# M_ch_Thu.net
KiCad netlist of a schematic drawn in Altium Designer
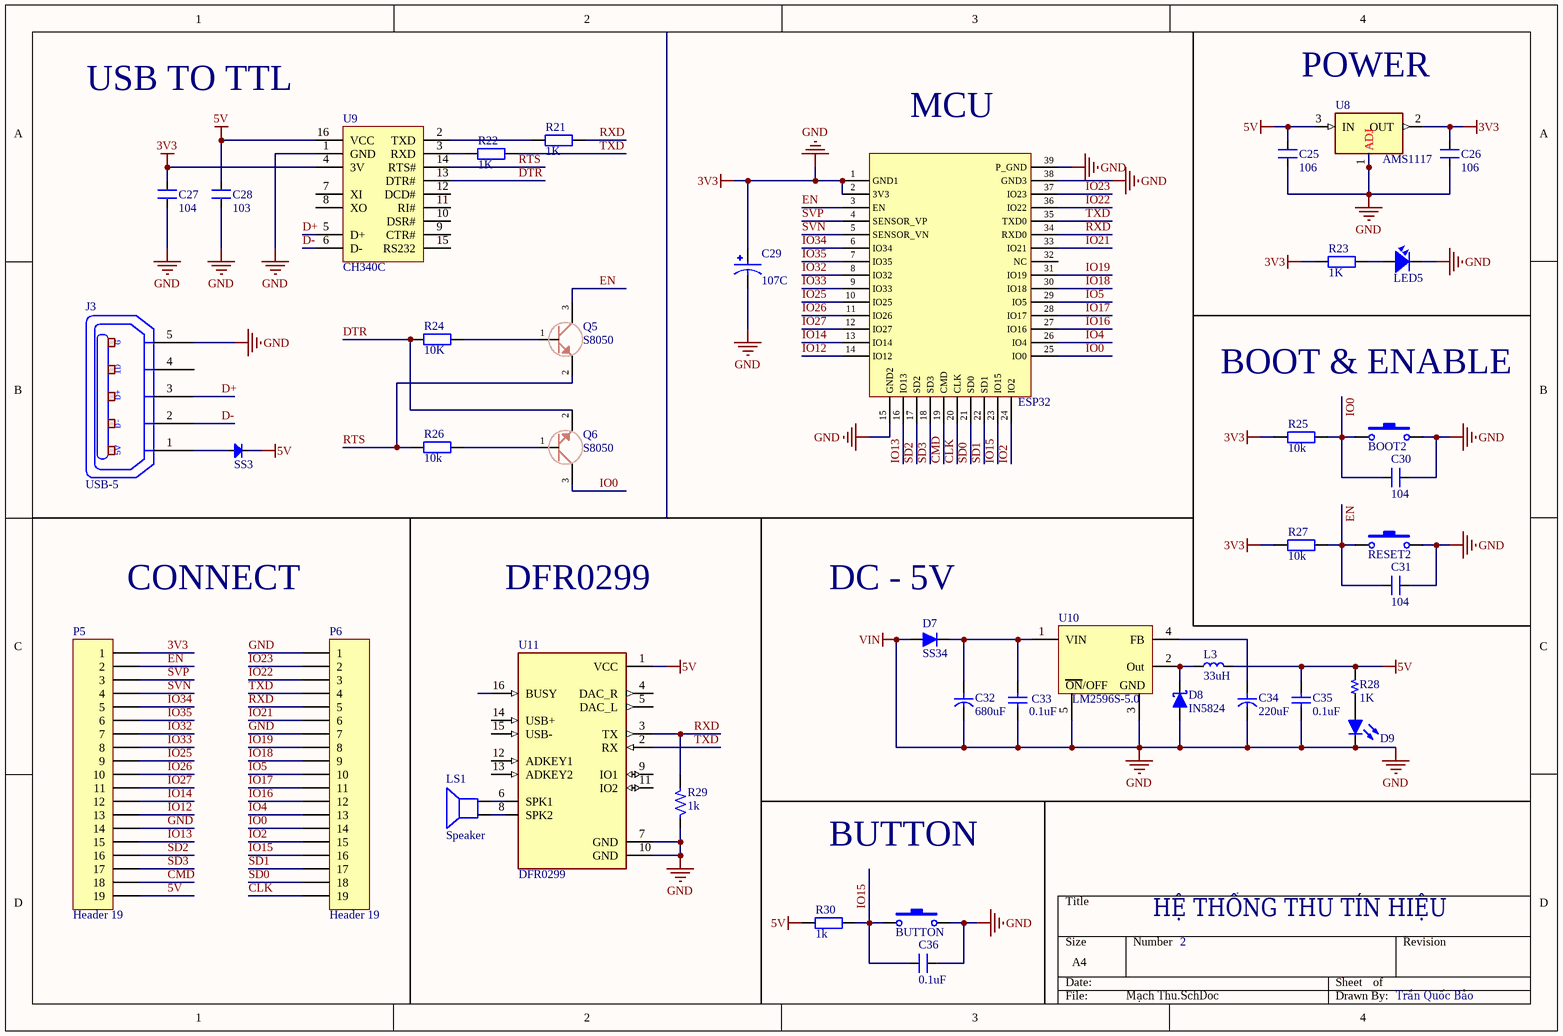
[diagram p0: Mạch Thu.SchDoc]

(export (version "E")
  (design (tool "Eeschema 10.0.6"))
  (components
    (comp (ref "BOOT2")
      (value "SW-SMD")
      (footprint "SW-SMD")
      (description "Switch")
      (fields (field (name "PUBLISHER") "Altium Limited"))
      (libsource (lib "My Library") (part "SW-SMD"))
    )
    (comp (ref "BUTTON")
      (value "SW-SMD")
      (footprint "SW-SMD")
      (description "Switch")
      (fields (field (name "PUBLISHER") "Altium Limited"))
      (libsource (lib "My Library") (part "SW-SMD"))
    )
    (comp (ref "C25")
      (value "106")
      (footprint "SM-0805")
      (description "Cap SMD")
      (libsource (lib "My Library") (part "CM"))
    )
    (comp (ref "C26")
      (value "106")
      (footprint "SM-0805")
      (description "Cap SMD")
      (libsource (lib "My Library") (part "CM"))
    )
    (comp (ref "C27")
      (value "104")
      (footprint "SM-0805")
      (description "Cap SMD")
      (libsource (lib "My Library") (part "CM"))
    )
    (comp (ref "C28")
      (value "103")
      (footprint "SM-0805")
      (description "Cap SMD")
      (libsource (lib "My Library") (part "CM"))
    )
    (comp (ref "C29")
      (value "107C")
      (footprint "CAP_TANTALUM_3528")
      (description "Capacitor, Tantalum")
      (fields (field (name "MF") "AVX") (field (name "MP") "TAJB475K025RNJ"))
      (libsource (lib "My Library") (part "CAP_TANTALUM_SMD"))
    )
    (comp (ref "C30")
      (value "104")
      (footprint "SM-0805")
      (description "Cap SMD")
      (libsource (lib "My Library") (part "CM"))
    )
    (comp (ref "C31")
      (value "104")
      (footprint "SM-0805")
      (description "Cap SMD")
      (libsource (lib "My Library") (part "CM"))
    )
    (comp (ref "C32")
      (value "680uF")
      (footprint "C SMD TAN 1206 (A)")
      (description "Capacitor pol")
      (libsource (lib "chipfc_altium_libs") (part "Capacitor"))
    )
    (comp (ref "C33")
      (value "0.1uF")
      (footprint "C 0805")
      (description "Capacitor non-pol")
      (libsource (lib "chipfc_altium_libs") (part "Capacitor NP"))
    )
    (comp (ref "C34")
      (value "220uF")
      (footprint "C SMD TAN 1206 (A)")
      (description "Capacitor pol")
      (libsource (lib "chipfc_altium_libs") (part "Capacitor"))
    )
    (comp (ref "C35")
      (value "0.1uF")
      (footprint "C 0805")
      (description "Capacitor non-pol")
      (libsource (lib "chipfc_altium_libs") (part "Capacitor NP"))
    )
    (comp (ref "C36")
      (value "0.1uF")
      (footprint "SM-0805")
      (description "Cap SMD")
      (libsource (lib "My Library") (part "CM"))
    )
    (comp (ref "D7")
      (value "SS34")
      (footprint "DO-35 (SOD27 )")
      (description "Default Diode")
      (libsource (lib "chipfc_altium_libs") (part "Diode"))
    )
    (comp (ref "D8")
      (value "IN5824")
      (footprint "DO-41")
      (description "Schottky Diode")
      (libsource (lib "chipfc_altium_libs") (part "Diode Schottky"))
    )
    (comp (ref "D9")
      (value "Led")
      (footprint "Led 0805 RED")
      (description "Typical LED")
      (libsource (lib "chipfc_altium_libs") (part "Led"))
    )
    (comp (ref "ESP32")
      (value "ESP32")
      (footprint "My Library:ESP_WROOM_32")
      (libsource (lib "My Library") (part "ESP-WROOM-32"))
    )
    (comp (ref "J3")
      (value "USB-5")
      (footprint "USB-M1")
      (fields
        (field (name "MANUFACTURER") "FCI")
        (field (name "MANUFACTURER PART NUMBER") "10118193-0001LF")
        (field (name ".CREATOR") "MM")
        (field (name ".CHECKED PCB") "RF")
        (field (name ".CHECKED SCH") "MM")
      )
      (libsource (lib "My Library") (part "USB-5"))
    )
    (comp (ref "L3")
      (value "33uH")
      (footprint "Inductor SMD 12x12x8")
      (description "Inductor")
      (libsource (lib "chipfc_altium_libs") (part "Inductor"))
    )
    (comp (ref "LED5") (value "LED") (footprint "LED 3512") (libsource (lib "My Library") (part "LED SMD")))
    (comp (ref "LS1")
      (value "Speaker")
      (footprint "SPEAKER")
      (description "Loudspeaker")
      (fields (field (name "PUBLISHER") "Altium Limited"))
      (libsource (lib "My Library") (part "Speaker"))
    )
    (comp (ref "P5")
      (value "Header 19")
      (footprint "HDR1X19")
      (description "Header, 19-Pin")
      (fields (field (name "PUBLISHER") "Altium Limited"))
      (libsource (lib "") (part "Header 19_1"))
    )
    (comp (ref "P6")
      (value "Header 19")
      (footprint "HDR1X19")
      (description "Header, 19-Pin")
      (fields (field (name "PUBLISHER") "Altium Limited"))
      (libsource (lib "My Library") (part "Header 19"))
    )
    (comp (ref "Q5")
      (value "S8050")
      (footprint "SOT23")
      (libsource (lib "My Library") (part "Transitor SMD"))
    )
    (comp (ref "Q6")
      (value "S8050")
      (footprint "SOT23")
      (libsource (lib "My Library") (part "Transitor SMD"))
    )
    (comp (ref "R21")
      (value "1K")
      (footprint "DIEN TRO 0805")
      (description "Resistor SMD 0805")
      (fields (field (name "Comment") "R0805") (field (name "PUBLISHER") "Altium Limited"))
      (libsource (lib "My Library") (part "R0805"))
    )
    (comp (ref "R22")
      (value "1K")
      (footprint "DIEN TRO 0805")
      (description "Resistor SMD 0805")
      (fields (field (name "Comment") "R0805") (field (name "PUBLISHER") "Altium Limited"))
      (libsource (lib "My Library") (part "R0805"))
    )
    (comp (ref "R23")
      (value "1K")
      (footprint "DIEN TRO 0805")
      (description "Resistor SMD 0805")
      (fields (field (name "Comment") "R0805") (field (name "PUBLISHER") "Altium Limited"))
      (libsource (lib "My Library") (part "R0805"))
    )
    (comp (ref "R24")
      (value "10K")
      (footprint "DIEN TRO 0805")
      (description "Resistor SMD 0805")
      (fields (field (name "Comment") "R0805") (field (name "PUBLISHER") "Altium Limited"))
      (libsource (lib "My Library") (part "R0805"))
    )
    (comp (ref "R25")
      (value "10k")
      (footprint "DIEN TRO 0805")
      (description "Resistor SMD 0805")
      (fields (field (name "Comment") "R0805") (field (name "PUBLISHER") "Altium Limited"))
      (libsource (lib "My Library") (part "R0805"))
    )
    (comp (ref "R26")
      (value "10k")
      (footprint "DIEN TRO 0805")
      (description "Resistor SMD 0805")
      (fields (field (name "Comment") "R0805") (field (name "PUBLISHER") "Altium Limited"))
      (libsource (lib "My Library") (part "R0805"))
    )
    (comp (ref "R27")
      (value "10k")
      (footprint "DIEN TRO 0805")
      (description "Resistor SMD 0805")
      (fields (field (name "Comment") "R0805") (field (name "PUBLISHER") "Altium Limited"))
      (libsource (lib "My Library") (part "R0805"))
    )
    (comp (ref "R28")
      (value "1K")
      (footprint "R 0805")
      (description "Resistor")
      (libsource (lib "chipfc_altium_libs") (part "Resistor"))
    )
    (comp (ref "R29")
      (value "1k")
      (footprint "R1/8W")
      (description "Resistor 1/4W")
      (libsource (lib "My Library") (part "R"))
    )
    (comp (ref "R30")
      (value "1k")
      (footprint "DIEN TRO 0805")
      (description "Resistor SMD 0805")
      (fields (field (name "Comment") "R0805") (field (name "PUBLISHER") "Altium Limited"))
      (libsource (lib "My Library") (part "R0805"))
    )
    (comp (ref "RESET2")
      (value "SW-SMD")
      (footprint "SW-SMD")
      (description "Switch")
      (fields (field (name "PUBLISHER") "Altium Limited"))
      (libsource (lib "My Library") (part "SW-SMD"))
    )
    (comp (ref "SS3")
      (value "Diode SMD")
      (footprint "DIO-SMD-106")
      (description "Default Diode")
      (fields (field (name "PUBLISHER") "Altium Limited"))
      (libsource (lib "My Library") (part "Diode SMD"))
    )
    (comp (ref "U8")
      (value "AMS1117")
      (footprint "SOT223-4N")
      (description "IC")
      (libsource (lib "My Library") (part "AMS1117"))
    )
    (comp (ref "U9")
      (value "CH340C")
      (footprint "SO16")
      (description "High and Low Side Driver")
      (fields (field (name "PUBLISHER") "Altium Limited"))
      (libsource (lib "My Library") (part "CH340G"))
    )
    (comp (ref "U10")
      (value "LM2596S-5.0")
      (footprint "TO-263-5")
      (description "Simple Switcher 3A Step-Down Voltage Regulator")
      (libsource (lib "chipfc_altium_libs") (part "LM2596S-5.0"))
    )
    (comp (ref "U11")
      (value "DFR0299")
      (footprint "MODULE_DFR0299")
      (description "Dfplayer - a Mini Mp3 Player")
      (libsource (lib "DFR0299") (part "DFR0299"))
    )
  )
  (nets
    (net (code "1") (name "/CLK") (class "Default")
      (node (ref "ESP32") (pin "20") (pinfunction "CLK_20") (pintype "passive"))
      (node (ref "P6") (pin "19") (pinfunction "19_19") (pintype "passive"))
    )
    (net (code "2") (name "/CMD") (class "Default")
      (node (ref "ESP32") (pin "19") (pinfunction "CMD_19") (pintype "passive"))
      (node (ref "P5") (pin "18") (pinfunction "18_18") (pintype "passive"))
    )
    (net (code "3") (name "/D+") (class "Default")
      (node (ref "J3") (pin "3") (pinfunction "P3_3") (pintype "passive"))
      (node (ref "U9") (pin "5") (pinfunction "D+_5") (pintype "passive"))
    )
    (net (code "4") (name "/D-") (class "Default")
      (node (ref "J3") (pin "2") (pinfunction "P2_2") (pintype "passive"))
      (node (ref "U9") (pin "6") (pinfunction "D-_6") (pintype "passive"))
    )
    (net (code "5") (name "/DTR") (class "Default")
      (node (ref "Q6") (pin "2") (pinfunction "E_2") (pintype "passive"))
      (node (ref "R24") (pin "1") (pinfunction "1_1") (pintype "passive"))
      (node (ref "U9") (pin "13") (pinfunction "DTR#_13") (pintype "passive"))
    )
    (net (code "6") (name "/EN") (class "Default")
      (node (ref "C31") (pin "2") (pinfunction "2_2") (pintype "passive"))
      (node (ref "ESP32") (pin "3") (pinfunction "EN_3") (pintype "passive"))
      (node (ref "P5") (pin "2") (pinfunction "2_2") (pintype "passive"))
      (node (ref "Q5") (pin "3") (pinfunction "C_3") (pintype "passive"))
      (node (ref "R27") (pin "2") (pinfunction "2_2") (pintype "passive"))
      (node (ref "RESET2") (pin "1") (pinfunction "1_1") (pintype "passive"))
    )
    (net (code "7") (name "/IO0") (class "Default")
      (node (ref "BOOT2") (pin "1") (pinfunction "1_1") (pintype "passive"))
      (node (ref "C30") (pin "2") (pinfunction "2_2") (pintype "passive"))
      (node (ref "ESP32") (pin "25") (pinfunction "IO0_25") (pintype "passive"))
      (node (ref "P6") (pin "14") (pinfunction "14_14") (pintype "passive"))
      (node (ref "Q6") (pin "3") (pinfunction "C_3") (pintype "passive"))
      (node (ref "R25") (pin "2") (pinfunction "2_2") (pintype "passive"))
    )
    (net (code "8") (name "/IO2") (class "Default")
      (node (ref "ESP32") (pin "24") (pinfunction "IO2_24") (pintype "passive"))
      (node (ref "P6") (pin "15") (pinfunction "15_15") (pintype "passive"))
    )
    (net (code "9") (name "/IO4") (class "Default")
      (node (ref "ESP32") (pin "26") (pinfunction "IO4_26") (pintype "passive"))
      (node (ref "P6") (pin "13") (pinfunction "13_13") (pintype "passive"))
    )
    (net (code "10") (name "/IO5") (class "Default")
      (node (ref "ESP32") (pin "29") (pinfunction "IO5_29") (pintype "passive"))
      (node (ref "P6") (pin "10") (pinfunction "10_10") (pintype "passive"))
    )
    (net (code "11") (name "/IO12") (class "Default")
      (node (ref "ESP32") (pin "14") (pinfunction "IO12_14") (pintype "passive"))
      (node (ref "P5") (pin "13") (pinfunction "13_13") (pintype "passive"))
    )
    (net (code "12") (name "/IO13") (class "Default")
      (node (ref "ESP32") (pin "16") (pinfunction "IO13_16") (pintype "passive"))
      (node (ref "P5") (pin "15") (pinfunction "15_15") (pintype "passive"))
    )
    (net (code "13") (name "/IO14") (class "Default")
      (node (ref "ESP32") (pin "13") (pinfunction "IO14_13") (pintype "passive"))
      (node (ref "P5") (pin "12") (pinfunction "12_12") (pintype "passive"))
    )
    (net (code "14") (name "/IO15") (class "Default")
      (node (ref "BUTTON") (pin "1") (pinfunction "1_1") (pintype "passive"))
      (node (ref "C36") (pin "2") (pinfunction "2_2") (pintype "passive"))
      (node (ref "ESP32") (pin "23") (pinfunction "IO15_23") (pintype "passive"))
      (node (ref "P6") (pin "16") (pinfunction "16_16") (pintype "passive"))
      (node (ref "R30") (pin "2") (pinfunction "2_2") (pintype "passive"))
    )
    (net (code "15") (name "/IO16") (class "Default")
      (node (ref "ESP32") (pin "27") (pinfunction "IO16_27") (pintype "passive"))
      (node (ref "P6") (pin "12") (pinfunction "12_12") (pintype "passive"))
    )
    (net (code "16") (name "/IO17") (class "Default")
      (node (ref "ESP32") (pin "28") (pinfunction "IO17_28") (pintype "passive"))
      (node (ref "P6") (pin "11") (pinfunction "11_11") (pintype "passive"))
    )
    (net (code "17") (name "/IO18") (class "Default")
      (node (ref "ESP32") (pin "30") (pinfunction "IO18_30") (pintype "passive"))
      (node (ref "P6") (pin "9") (pinfunction "9_9") (pintype "passive"))
    )
    (net (code "18") (name "/IO19") (class "Default")
      (node (ref "ESP32") (pin "31") (pinfunction "IO19_31") (pintype "passive"))
      (node (ref "P6") (pin "8") (pinfunction "8_8") (pintype "passive"))
    )
    (net (code "19") (name "/IO21") (class "Default")
      (node (ref "ESP32") (pin "33") (pinfunction "IO21_33") (pintype "passive"))
      (node (ref "P6") (pin "6") (pinfunction "6_6") (pintype "passive"))
    )
    (net (code "20") (name "/IO22") (class "Default")
      (node (ref "ESP32") (pin "36") (pinfunction "IO22_36") (pintype "passive"))
      (node (ref "P6") (pin "3") (pinfunction "3_3") (pintype "passive"))
    )
    (net (code "21") (name "/IO23") (class "Default")
      (node (ref "ESP32") (pin "37") (pinfunction "IO23_37") (pintype "passive"))
      (node (ref "P6") (pin "2") (pinfunction "2_2") (pintype "passive"))
    )
    (net (code "22") (name "/IO25") (class "Default")
      (node (ref "ESP32") (pin "10") (pinfunction "IO25_10") (pintype "passive"))
      (node (ref "P5") (pin "9") (pinfunction "9_9") (pintype "passive"))
    )
    (net (code "23") (name "/IO26") (class "Default")
      (node (ref "ESP32") (pin "11") (pinfunction "IO26_11") (pintype "passive"))
      (node (ref "P5") (pin "10") (pinfunction "10_10") (pintype "passive"))
    )
    (net (code "24") (name "/IO27") (class "Default")
      (node (ref "ESP32") (pin "12") (pinfunction "IO27_12") (pintype "passive"))
      (node (ref "P5") (pin "11") (pinfunction "11_11") (pintype "passive"))
    )
    (net (code "25") (name "/IO32") (class "Default")
      (node (ref "ESP32") (pin "8") (pinfunction "IO32_8") (pintype "passive"))
      (node (ref "P5") (pin "7") (pinfunction "7_7") (pintype "passive"))
    )
    (net (code "26") (name "/IO33") (class "Default")
      (node (ref "ESP32") (pin "9") (pinfunction "IO33_9") (pintype "passive"))
      (node (ref "P5") (pin "8") (pinfunction "8_8") (pintype "passive"))
    )
    (net (code "27") (name "/IO34") (class "Default")
      (node (ref "ESP32") (pin "6") (pinfunction "IO34_6") (pintype "passive"))
      (node (ref "P5") (pin "5") (pinfunction "5_5") (pintype "passive"))
    )
    (net (code "28") (name "/IO35") (class "Default")
      (node (ref "ESP32") (pin "7") (pinfunction "IO35_7") (pintype "passive"))
      (node (ref "P5") (pin "6") (pinfunction "6_6") (pintype "passive"))
    )
    (net (code "29") (name "/RTS") (class "Default")
      (node (ref "Q5") (pin "2") (pinfunction "E_2") (pintype "passive"))
      (node (ref "R26") (pin "1") (pinfunction "1_1") (pintype "passive"))
      (node (ref "U9") (pin "14") (pinfunction "RTS#_14") (pintype "passive"))
    )
    (net (code "30") (name "/RXD") (class "Default")
      (node (ref "ESP32") (pin "34") (pinfunction "RXD0_34") (pintype "passive"))
      (node (ref "P6") (pin "5") (pinfunction "5_5") (pintype "passive"))
      (node (ref "R21") (pin "2") (pinfunction "2_2") (pintype "passive"))
      (node (ref "R29") (pin "2") (pinfunction "2_2") (pintype "passive"))
      (node (ref "U11") (pin "3") (pinfunction "TX_3") (pintype "output"))
    )
    (net (code "31") (name "/SD0") (class "Default")
      (node (ref "ESP32") (pin "21") (pinfunction "SD0_21") (pintype "passive"))
      (node (ref "P6") (pin "18") (pinfunction "18_18") (pintype "passive"))
    )
    (net (code "32") (name "/SD1") (class "Default")
      (node (ref "ESP32") (pin "22") (pinfunction "SD1_22") (pintype "passive"))
      (node (ref "P6") (pin "17") (pinfunction "17_17") (pintype "passive"))
    )
    (net (code "33") (name "/SD2") (class "Default")
      (node (ref "ESP32") (pin "17") (pinfunction "SD2_17") (pintype "passive"))
      (node (ref "P5") (pin "16") (pinfunction "16_16") (pintype "passive"))
    )
    (net (code "34") (name "/SD3") (class "Default")
      (node (ref "ESP32") (pin "18") (pinfunction "SD3_18") (pintype "passive"))
      (node (ref "P5") (pin "17") (pinfunction "17_17") (pintype "passive"))
    )
    (net (code "35") (name "/SVN") (class "Default")
      (node (ref "ESP32") (pin "5") (pinfunction "SENSOR_VN_5") (pintype "passive"))
      (node (ref "P5") (pin "4") (pinfunction "4_4") (pintype "passive"))
    )
    (net (code "36") (name "/SVP") (class "Default")
      (node (ref "ESP32") (pin "4") (pinfunction "SENSOR_VP_4") (pintype "passive"))
      (node (ref "P5") (pin "3") (pinfunction "3_3") (pintype "passive"))
    )
    (net (code "37") (name "/TXD") (class "Default")
      (node (ref "ESP32") (pin "35") (pinfunction "TXD0_35") (pintype "passive"))
      (node (ref "P6") (pin "4") (pinfunction "4_4") (pintype "passive"))
      (node (ref "R22") (pin "2") (pinfunction "2_2") (pintype "passive"))
      (node (ref "U11") (pin "2") (pinfunction "RX_2") (pintype "input"))
    )
    (net (code "38") (name "3V3") (class "Default")
      (node (ref "BOOT2") (pin "2") (pinfunction "2_2") (pintype "passive"))
      (node (ref "BUTTON") (pin "2") (pinfunction "2_2") (pintype "passive"))
      (node (ref "C25") (pin "1") (pinfunction "1_1") (pintype "passive"))
      (node (ref "C26") (pin "1") (pinfunction "1_1") (pintype "passive"))
      (node (ref "C26") (pin "2") (pinfunction "2_2") (pintype "passive"))
      (node (ref "C27") (pin "1") (pinfunction "1_1") (pintype "passive"))
      (node (ref "C27") (pin "2") (pinfunction "2_2") (pintype "passive"))
      (node (ref "C28") (pin "1") (pinfunction "1_1") (pintype "passive"))
      (node (ref "C29") (pin "1") (pinfunction "1_1") (pintype "passive"))
      (node (ref "C29") (pin "2") (pinfunction "2_2") (pintype "passive"))
      (node (ref "C30") (pin "1") (pinfunction "1_1") (pintype "passive"))
      (node (ref "C31") (pin "1") (pinfunction "1_1") (pintype "passive"))
      (node (ref "C32") (pin "2") (pinfunction "2_2") (pintype "passive"))
      (node (ref "C33") (pin "2") (pinfunction "2_2") (pintype "passive"))
      (node (ref "C34") (pin "2") (pinfunction "2_2") (pintype "passive"))
      (node (ref "C35") (pin "2") (pinfunction "2_2") (pintype "passive"))
      (node (ref "C36") (pin "1") (pinfunction "1_1") (pintype "passive"))
      (node (ref "D7") (pin "1") (pinfunction "A_1") (pintype "passive"))
      (node (ref "D8") (pin "1") (pinfunction "A_1") (pintype "passive"))
      (node (ref "D9") (pin "2") (pinfunction "K_2") (pintype "passive"))
      (node (ref "ESP32") (pin "1") (pinfunction "GND1_1") (pintype "passive"))
      (node (ref "ESP32") (pin "15") (pinfunction "GND2_15") (pintype "passive"))
      (node (ref "ESP32") (pin "2") (pinfunction "3V3_2") (pintype "passive"))
      (node (ref "ESP32") (pin "38") (pinfunction "GND3_38") (pintype "passive"))
      (node (ref "ESP32") (pin "39") (pinfunction "P_GND_39") (pintype "passive"))
      (node (ref "J3") (pin "5") (pinfunction "P5_5") (pintype "passive"))
      (node (ref "LED5") (pin "2") (pinfunction "2_2") (pintype "passive"))
      (node (ref "P5") (pin "1") (pinfunction "1_1") (pintype "passive"))
      (node (ref "P5") (pin "14") (pinfunction "14_14") (pintype "passive"))
      (node (ref "P6") (pin "1") (pinfunction "1_1") (pintype "passive"))
      (node (ref "P6") (pin "7") (pinfunction "7_7") (pintype "passive"))
      (node (ref "R23") (pin "1") (pinfunction "1_1") (pintype "passive"))
      (node (ref "R25") (pin "1") (pinfunction "1_1") (pintype "passive"))
      (node (ref "R27") (pin "1") (pinfunction "1_1") (pintype "passive"))
      (node (ref "R29") (pin "1") (pinfunction "1_1") (pintype "passive"))
      (node (ref "RESET2") (pin "2") (pinfunction "2_2") (pintype "passive"))
      (node (ref "U10") (pin "3") (pinfunction "GND_3") (pintype "passive"))
      (node (ref "U10") (pin "5") (pinfunction "~{ON}/OFF_5") (pintype "passive"))
      (node (ref "U11") (pin "10") (pinfunction "GND_10") (pintype "power_in"))
      (node (ref "U11") (pin "7") (pinfunction "GND_7") (pintype "power_in"))
      (node (ref "U8") (pin "1") (pinfunction "ADJ_1") (pintype "passive"))
      (node (ref "U8") (pin "2") (pinfunction "OUT_2") (pintype "output"))
      (node (ref "U9") (pin "1") (pinfunction "GND_1") (pintype "passive"))
      (node (ref "U9") (pin "4") (pinfunction "3V_4") (pintype "passive"))
    )
    (net (code "39") (name "5V") (class "Default")
      (node (ref "C25") (pin "2") (pinfunction "2_2") (pintype "passive"))
      (node (ref "C28") (pin "2") (pinfunction "2_2") (pintype "passive"))
      (node (ref "C35") (pin "1") (pinfunction "1_1") (pintype "passive"))
      (node (ref "L3") (pin "2") (pinfunction "2_2") (pintype "passive"))
      (node (ref "P5") (pin "19") (pinfunction "19_19") (pintype "passive"))
      (node (ref "R28") (pin "2") (pinfunction "2_2") (pintype "passive"))
      (node (ref "R30") (pin "1") (pinfunction "1_1") (pintype "passive"))
      (node (ref "SS3") (pin "2") (pinfunction "K_2") (pintype "passive"))
      (node (ref "U11") (pin "1") (pinfunction "VCC_1") (pintype "power_in"))
      (node (ref "U8") (pin "3") (pinfunction "IN_3") (pintype "input"))
      (node (ref "U9") (pin "16") (pinfunction "VCC_16") (pintype "passive"))
    )
    (net (code "40") (name "Net-(D7-K)") (class "Default")
      (node (ref "C32") (pin "1") (pinfunction "1_1") (pintype "passive"))
      (node (ref "C33") (pin "1") (pinfunction "1_1") (pintype "passive"))
      (node (ref "D7") (pin "2") (pinfunction "K_2") (pintype "passive"))
      (node (ref "U10") (pin "1") (pinfunction "VIN_1") (pintype "passive"))
    )
    (net (code "41") (name "Net-(D8-K)") (class "Default")
      (node (ref "D8") (pin "2") (pinfunction "K_2") (pintype "passive"))
      (node (ref "L3") (pin "1") (pinfunction "1_1") (pintype "passive"))
      (node (ref "U10") (pin "2") (pinfunction "Out_2") (pintype "passive"))
    )
    (net (code "42") (name "Net-(D9-A)") (class "Default")
      (node (ref "D9") (pin "1") (pinfunction "A_1") (pintype "passive"))
      (node (ref "R28") (pin "1") (pinfunction "1_1") (pintype "passive"))
    )
    (net (code "43") (name "Net-(J3-P1)") (class "Default")
      (node (ref "J3") (pin "1") (pinfunction "P1_1") (pintype "passive"))
      (node (ref "SS3") (pin "1") (pinfunction "A_1") (pintype "passive"))
    )
    (net (code "44") (name "Net-(LED5-Pad1)") (class "Default")
      (node (ref "LED5") (pin "1") (pinfunction "1_1") (pintype "passive"))
      (node (ref "R23") (pin "2") (pinfunction "2_2") (pintype "passive"))
    )
    (net (code "45") (name "Net-(Q5-B)") (class "Default")
      (node (ref "Q5") (pin "1") (pinfunction "B_1") (pintype "passive"))
      (node (ref "R24") (pin "2") (pinfunction "2_2") (pintype "passive"))
    )
    (net (code "46") (name "Net-(Q6-B)") (class "Default")
      (node (ref "Q6") (pin "1") (pinfunction "B_1") (pintype "passive"))
      (node (ref "R26") (pin "2") (pinfunction "2_2") (pintype "passive"))
    )
    (net (code "47") (name "Net-(U9-RXD)") (class "Default")
      (node (ref "R22") (pin "1") (pinfunction "1_1") (pintype "passive"))
      (node (ref "U9") (pin "3") (pinfunction "RXD_3") (pintype "passive"))
    )
    (net (code "48") (name "Net-(U9-TXD)") (class "Default")
      (node (ref "R21") (pin "1") (pinfunction "1_1") (pintype "passive"))
      (node (ref "U9") (pin "2") (pinfunction "TXD_2") (pintype "passive"))
    )
    (net (code "49") (name "Net-(U10-FB)") (class "Default")
      (node (ref "C34") (pin "1") (pinfunction "1_1") (pintype "passive"))
      (node (ref "U10") (pin "4") (pinfunction "FB_4") (pintype "passive"))
    )
    (net (code "50") (name "Net-(U11-SPK1)") (class "Default")
      (node (ref "LS1") (pin "2") (pinfunction "2_2") (pintype "passive"))
      (node (ref "U11") (pin "6") (pinfunction "SPK1_6") (pintype "passive"))
    )
    (net (code "51") (name "Net-(U11-SPK2)") (class "Default")
      (node (ref "LS1") (pin "1") (pinfunction "1_1") (pintype "passive"))
      (node (ref "U11") (pin "8") (pinfunction "SPK2_8") (pintype "passive"))
    )
    (net (code "52") (name "unconnected-(ESP32-NC-Pad32)") (class "Default")
      (node (ref "ESP32") (pin "32") (pinfunction "NC_32") (pintype "passive"))
    )
    (net (code "53") (name "unconnected-(J3-P4-Pad4)") (class "Default")
      (node (ref "J3") (pin "4") (pinfunction "P4_4") (pintype "passive"))
    )
    (net (code "54") (name "unconnected-(U9-CTR#-Pad9)") (class "Default")
      (node (ref "U9") (pin "9") (pinfunction "CTR#_9") (pintype "passive"))
    )
    (net (code "55") (name "unconnected-(U9-DCD#-Pad12)") (class "Default")
      (node (ref "U9") (pin "12") (pinfunction "DCD#_12") (pintype "passive"))
    )
    (net (code "56") (name "unconnected-(U9-DSR#-Pad10)") (class "Default")
      (node (ref "U9") (pin "10") (pinfunction "DSR#_10") (pintype "passive"))
    )
    (net (code "57") (name "unconnected-(U9-RI#-Pad11)") (class "Default")
      (node (ref "U9") (pin "11") (pinfunction "RI#_11") (pintype "passive"))
    )
    (net (code "58") (name "unconnected-(U9-RS232-Pad15)") (class "Default")
      (node (ref "U9") (pin "15") (pinfunction "RS232_15") (pintype "passive"))
    )
    (net (code "59") (name "unconnected-(U9-XI-Pad7)") (class "Default")
      (node (ref "U9") (pin "7") (pinfunction "XI_7") (pintype "passive"))
    )
    (net (code "60") (name "unconnected-(U9-XO-Pad8)") (class "Default")
      (node (ref "U9") (pin "8") (pinfunction "XO_8") (pintype "passive"))
    )
    (net (code "61") (name "unconnected-(U10-PAD-Pad6)") (class "Default")
      (node (ref "U10") (pin "6") (pinfunction "PAD_6") (pintype "passive"))
    )
    (net (code "62") (name "unconnected-(U11-ADKEY1-Pad12)") (class "Default")
      (node (ref "U11") (pin "12") (pinfunction "ADKEY1_12") (pintype "input"))
    )
    (net (code "63") (name "unconnected-(U11-ADKEY2-Pad13)") (class "Default")
      (node (ref "U11") (pin "13") (pinfunction "ADKEY2_13") (pintype "input"))
    )
    (net (code "64") (name "unconnected-(U11-BUSY-Pad16)") (class "Default")
      (node (ref "U11") (pin "16") (pinfunction "BUSY_16") (pintype "input"))
    )
    (net (code "65") (name "unconnected-(U11-DAC_L-Pad5)") (class "Default")
      (node (ref "U11") (pin "5") (pinfunction "DAC_L_5") (pintype "output"))
    )
    (net (code "66") (name "unconnected-(U11-DAC_R-Pad4)") (class "Default")
      (node (ref "U11") (pin "4") (pinfunction "DAC_R_4") (pintype "output"))
    )
    (net (code "67") (name "unconnected-(U11-IO1-Pad9)") (class "Default")
      (node (ref "U11") (pin "9") (pinfunction "IO1_9") (pintype "bidirectional"))
    )
    (net (code "68") (name "unconnected-(U11-IO2-Pad11)") (class "Default")
      (node (ref "U11") (pin "11") (pinfunction "IO2_11") (pintype "bidirectional"))
    )
    (net (code "69") (name "unconnected-(U11-USB+-Pad14)") (class "Default")
      (node (ref "U11") (pin "14") (pinfunction "USB+_14") (pintype "input"))
    )
    (net (code "70") (name "unconnected-(U11-USB--Pad15)") (class "Default")
      (node (ref "U11") (pin "15") (pinfunction "USB-_15") (pintype "input"))
    )
  )
)
